# Power_Board.net
KiCad netlist of a schematic drawn in Altium Designer
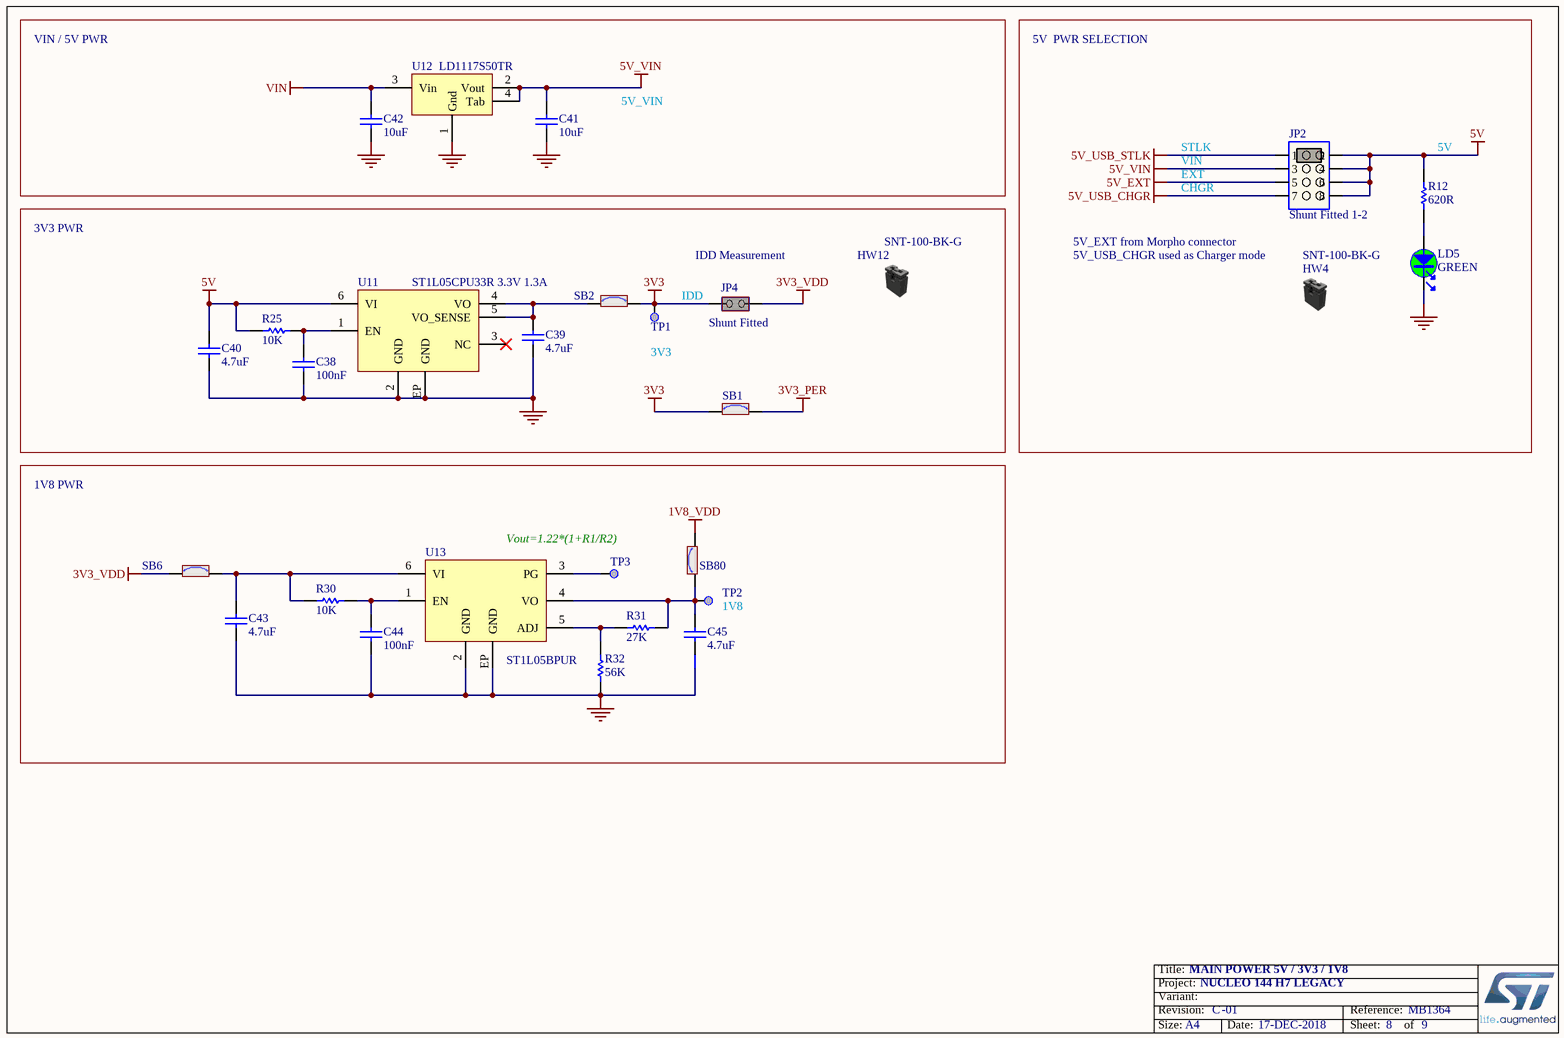
[diagram p0: Power_Board.SchDoc]

(export (version "E")
  (design (tool "Eeschema 10.0.6"))
  (components
    (comp (ref "C38")
      (value "100nF")
      (footprint "C0402")
      (description "Capacitor, MLCC, 100nF, 16V, X7R, 10%, 0402, T=0.5mm")
      (fields
        (field (name "INTERNAL_PART_NUMBER") "MCD-00006")
        (field (name "MANUFACTURER_PART_NUMBER") "CC0402KRX7R7BB104")
        (field (name "PROVIDED_BY") "SUBCO")
      )
      (libsource (lib "MCD_PARTS_database") (part "Capacitor"))
    )
    (comp (ref "C39")
      (value "4.7uF")
      (footprint "C0603")
      (description "Capacitor, MLCC, 4.7µF, 10V, X5R, 20%, 0603, T=0,8mm")
      (fields
        (field (name "INTERNAL_PART_NUMBER") "MCD-01121")
        (field (name "MANUFACTURER_PART_NUMBER") "GRM188R61A475ME15")
        (field (name "PROVIDED_BY") "SUBCO")
      )
      (libsource (lib "MCD_PARTS_database") (part "Capacitor"))
    )
    (comp (ref "C40")
      (value "4.7uF")
      (footprint "C0603")
      (description "Capacitor, MLCC, 4.7uF, 16V, X5R, 20%, 0603, T=0,8mm")
      (fields
        (field (name "INTERNAL_PART_NUMBER") "MCD-00097")
        (field (name "MANUFACTURER_PART_NUMBER") "GRM188R61C475KE11")
        (field (name "PROVIDED_BY") "SUBCO")
      )
      (libsource (lib "MCD_PARTS_database") (part "Capacitor"))
    )
    (comp (ref "C41")
      (value "10uF")
      (footprint "C0805")
      (description "Capacitor, MLCC, 10uF, 25V, X5R, 10%, 0805, T=0,85mm")
      (fields
        (field (name "INTERNAL_PART_NUMBER") "MCD-00014")
        (field (name "MANUFACTURER_PART_NUMBER") "CC0805KRX5R8BB106")
        (field (name "PROVIDED_BY") "SUBCO")
      )
      (libsource (lib "MCD_PARTS_database") (part "Capacitor"))
    )
    (comp (ref "C42")
      (value "10uF")
      (footprint "C0805")
      (description "Capacitor, MLCC, 10uF, 25V, X5R, 10%, 0805, T=0,85mm")
      (fields
        (field (name "INTERNAL_PART_NUMBER") "MCD-00014")
        (field (name "MANUFACTURER_PART_NUMBER") "CC0805KRX5R8BB106")
        (field (name "PROVIDED_BY") "SUBCO")
      )
      (libsource (lib "MCD_PARTS_database") (part "Capacitor"))
    )
    (comp (ref "C43")
      (value "4.7uF")
      (footprint "C0603")
      (description "Capacitor, MLCC, 4.7uF, 16V, X5R, 20%, 0603, T=0,8mm")
      (fields
        (field (name "INTERNAL_PART_NUMBER") "MCD-00097")
        (field (name "MANUFACTURER_PART_NUMBER") "GRM188R61C475KE11")
        (field (name "PROVIDED_BY") "SUBCO")
      )
      (libsource (lib "MCD_PARTS_database") (part "Capacitor"))
    )
    (comp (ref "C44")
      (value "100nF")
      (footprint "C0603")
      (description "Capacitor, MLCC, 100nF, 6V3, X5R, 10%, 0603, T=0,8mm")
      (fields
        (field (name "INTERNAL_PART_NUMBER") "MCD-00237")
        (field (name "MANUFACTURER_PART_NUMBER") "CC0603KRX5R5BB104")
        (field (name "PROVIDED_BY") "SUBCO")
      )
      (libsource (lib "MCD_PARTS_database") (part "Capacitor"))
    )
    (comp (ref "C45")
      (value "4.7uF")
      (footprint "C0603")
      (description "Capacitor, MLCC, 4.7µF, 10V, X5R, 20%, 0603, T=0,8mm")
      (fields
        (field (name "INTERNAL_PART_NUMBER") "MCD-01121")
        (field (name "MANUFACTURER_PART_NUMBER") "GRM188R61A475ME15")
        (field (name "PROVIDED_BY") "SUBCO")
      )
      (libsource (lib "MCD_PARTS_database") (part "Capacitor"))
    )
    (comp (ref "HW4")
      (value "SNT-100-BK-G")
      (description "SHUNT 2.54mm BLACK")
      (fields
        (field (name "INTERNAL_PART_NUMBER") "MCD-00043")
        (field (name "MANUFACTURER") "SAMTEC")
        (field (name "PROVIDED_BY") "SUBCO")
      )
      (libsource (lib "MCD_PARTS_database") (part "Shunt Black 2.54mm"))
    )
    (comp (ref "HW12")
      (value "SNT-100-BK-G")
      (description "SHUNT 2.54mm BLACK")
      (fields
        (field (name "INTERNAL_PART_NUMBER") "MCD-00043")
        (field (name "MANUFACTURER") "SAMTEC")
        (field (name "PROVIDED_BY") "SUBCO")
      )
      (libsource (lib "MCD_PARTS_database") (part "Shunt Black 2.54mm"))
    )
    (comp (ref "JP2")
      (value "Shunt Fitted 1-2")
      (footprint "CON_SAMTEC_TSW-104-07-X-D")
      (description "Header, 4x2, 2,54mm, VR, TH, Height 5.84mm/2.54mm - Shunt Fitted 1-2")
      (fields
        (field (name "INTERNAL_PART_NUMBER") "MCD-00686")
        (field (name "MANUFACTURER_PART_NUMBER") "TSW-104-07-x-D")
        (field (name "PROVIDED_BY") "SUBCO")
      )
      (libsource (lib "MCD_PARTS_database") (part "Jumper_Header 4x2 Fitted 1-2"))
    )
    (comp (ref "JP4")
      (value "Shunt Fitted")
      (footprint "CON_SAMTEC_TSW-102-07-G-S")
      (description "Header, 2x1, 2,54mm, VR, TH, Height 5.84mm/2.54mm - Shunt Fitted by default")
      (fields
        (field (name "INTERNAL_PART_NUMBER") "MCD-00683")
        (field (name "MANUFACTURER_PART_NUMBER") "TSW-102-07-x-S")
        (field (name "PROVIDED_BY") "SUBCO")
      )
      (libsource (lib "MCD_PARTS_database") (part "Jumper_Header 2x1 Fitted"))
    )
    (comp (ref "LD5")
      (value "GREEN")
      (footprint "LED_0603_OSRAM_LG-Q396-PS-35_GREEN_1A2K_H0P4")
      (description "LED Green, 0603 SMD, Forward Voltage Typ=2V, Max=2.5V")
      (fields
        (field (name "INTERNAL_PART_NUMBER") "MCD-00588")
        (field (name "MANUFACTURER_PART_NUMBER") "LG Q396-PS-35")
        (field (name "PROVIDED_BY") "SUBCO")
      )
      (libsource (lib "MCD_PARTS_database") (part "LED_green"))
    )
    (comp (ref "R12")
      (value "620R")
      (footprint "R0603")
      (description "Resistor,620R,0603,1%,1/10W")
      (fields
        (field (name "INTERNAL_PART_NUMBER") "MCD-00500")
        (field (name "MANUFACTURER_PART_NUMBER") "RC0603FR-07620RL")
        (field (name "PROVIDED_BY") "SUBCO")
      )
      (libsource (lib "MCD_PARTS_database") (part "Resistor"))
    )
    (comp (ref "R25")
      (value "10K")
      (footprint "R0402")
      (description "Resistor,10K,0402,1%,1/16W")
      (fields
        (field (name "INTERNAL_PART_NUMBER") "MCD-00053")
        (field (name "MANUFACTURER_PART_NUMBER") "RC0402FR-0710KL")
        (field (name "PROVIDED_BY") "SUBCO")
      )
      (libsource (lib "MCD_PARTS_database") (part "Resistor"))
    )
    (comp (ref "R30")
      (value "10K")
      (footprint "R0402")
      (description "Resistor,10K,0402,1%,1/16W")
      (fields
        (field (name "INTERNAL_PART_NUMBER") "MCD-00053")
        (field (name "MANUFACTURER_PART_NUMBER") "RC0402FR-0710KL")
        (field (name "PROVIDED_BY") "SUBCO")
      )
      (libsource (lib "MCD_PARTS_database") (part "Resistor"))
    )
    (comp (ref "R31")
      (value "27K")
      (footprint "R0402")
      (description "Resistor,27K,0402,1%,1/16W")
      (fields
        (field (name "INTERNAL_PART_NUMBER") "MCD-00443")
        (field (name "MANUFACTURER_PART_NUMBER") "RC0402FR-0727KL")
        (field (name "PROVIDED_BY") "SUBCO")
      )
      (libsource (lib "MCD_PARTS_database") (part "Resistor"))
    )
    (comp (ref "R32")
      (value "56K")
      (footprint "R0402")
      (description "Resistor,56K,0402,1%,1/16W")
      (fields
        (field (name "INTERNAL_PART_NUMBER") "MCD-00493")
        (field (name "MANUFACTURER_PART_NUMBER") "RC0402FR-0756KL")
        (field (name "PROVIDED_BY") "SUBCO")
      )
      (libsource (lib "MCD_PARTS_database") (part "Resistor"))
    )
    (comp (ref "SB1")
      (value "SB_ON")
      (footprint "SOLDER-BRIDGE_R0603-0R")
      (description "Solder Bridge ON")
      (fields
        (field (name "INTERNAL_PART_NUMBER") "MCD-00071")
        (field (name "MANUFACTURER_PART_NUMBER") "RC0603JR-070RL")
        (field (name "PROVIDED_BY") "SUBCO")
      )
      (libsource (lib "MCD_PARTS_database") (part "SB_ON"))
    )
    (comp (ref "SB2")
      (value "SB_ON")
      (footprint "SOLDER-BRIDGE_R0603-0R")
      (description "Solder Bridge ON")
      (fields
        (field (name "INTERNAL_PART_NUMBER") "MCD-00071")
        (field (name "MANUFACTURER_PART_NUMBER") "RC0603JR-070RL")
        (field (name "PROVIDED_BY") "SUBCO")
      )
      (libsource (lib "MCD_PARTS_database") (part "SB_ON"))
    )
    (comp (ref "SB6")
      (value "SB_ON")
      (footprint "SOLDER-BRIDGE_R0603-0R")
      (description "Solder Bridge ON")
      (fields
        (field (name "INTERNAL_PART_NUMBER") "MCD-00071")
        (field (name "MANUFACTURER_PART_NUMBER") "RC0603JR-070RL")
        (field (name "PROVIDED_BY") "SUBCO")
      )
      (libsource (lib "MCD_PARTS_database") (part "SB_ON"))
    )
    (comp (ref "SB80")
      (value "SB_ON")
      (footprint "SOLDER-BRIDGE_R0603-0R")
      (description "Solder Bridge ON")
      (fields
        (field (name "INTERNAL_PART_NUMBER") "MCD-00071")
        (field (name "MANUFACTURER_PART_NUMBER") "RC0603JR-070RL")
        (field (name "PROVIDED_BY") "SUBCO")
      )
      (libsource (lib "") (part "SB_ON_1"))
    )
    (comp (ref "TP1")
      (value "Test Point")
      (footprint "TP_SMD_1MM")
      (description "Test Point 1mm")
      (fields (field (name "INTERNAL_PART_NUMBER") "MCD-00074") (field (name "MANUFACTURER") "n/a"))
      (libsource (lib "") (part "Test Point_1"))
    )
    (comp (ref "TP2")
      (value "Test Point")
      (footprint "TP_SMD_1MM")
      (description "Test Point 1mm")
      (fields
        (field (name "INTERNAL_PART_NUMBER") "MCD-00074")
        (field (name "MANUFACTURER_PART_NUMBER") "n/a")
      )
      (libsource (lib "MCD_PARTS_database") (part "Test Point"))
    )
    (comp (ref "TP3")
      (value "Test Point")
      (footprint "TP_SMD_1MM")
      (description "Test Point 1mm")
      (fields
        (field (name "INTERNAL_PART_NUMBER") "MCD-00074")
        (field (name "MANUFACTURER_PART_NUMBER") "n/a")
      )
      (libsource (lib "MCD_PARTS_database") (part "Test Point"))
    )
    (comp (ref "U11")
      (value "ST1L05CPU33R 3.3V 1.3A")
      (footprint "ICC_DFN6-EPAD_3X3_P095")
      (description "LDO, 3.3V, 1.3A, Very low quiescent current BiCMOS voltage regulator")
      (fields
        (field (name "INTERNAL_PART_NUMBER") "MCD-01025")
        (field (name "MANUFACTURER_PART_NUMBER") "ST1L05CPU33R")
        (field (name "PROVIDED_BY") "SUBCO with ST control")
      )
      (libsource (lib "MCD_PARTS_database") (part "ST1L05CPU33R"))
    )
    (comp (ref "U12")
      (value "LD1117S50TR")
      (footprint "REG_SOT223-TAB")
      (description "IC REG LDO 5V 0.8A SOT223")
      (fields
        (field (name "INTERNAL_PART_NUMBER") "MCD-00088")
        (field (name "MANUFACTURER") "STMICROELECTRONICS")
        (field (name "PROVIDED_BY") "SUBCO with ST control")
      )
      (libsource (lib "MCD_PARTS_database") (part "LD1117S50TR"))
    )
    (comp (ref "U13")
      (value "ST1L05BPUR")
      (footprint "ICC_DFN6-EPAD_3X3_P095")
      (description "LDO Linear Voltage Regulator IC Positive Adjustable 1 Output Adjustable 1.3A 6-DFN (3x3)")
      (fields
        (field (name "INTERNAL_PART_NUMBER") "MCD-00581")
        (field (name "MANUFACTURER") "STMICROELECTRONICS")
        (field (name "PROVIDED_BY") "SUBCO with ST control")
      )
      (libsource (lib "MCD_PARTS_database") (part "ST1L05BPUR"))
    )
  )
  (nets
    (net (code "1") (name "1V8_VDD") (class "Default")
      (node (ref "SB80") (pin "2") (pinfunction "2_2") (pintype "passive"))
    )
    (net (code "2") (name "3V3") (class "Default")
      (node (ref "JP4") (pin "1") (pinfunction "COMMON_1") (pintype "passive"))
      (node (ref "SB1") (pin "1") (pinfunction "1_1") (pintype "passive"))
      (node (ref "SB2") (pin "2") (pinfunction "2_2") (pintype "passive"))
      (node (ref "TP1") (pin "1") (pinfunction "1_1") (pintype "passive"))
    )
    (net (code "3") (name "3V3_PER") (class "Default")
      (node (ref "SB1") (pin "2") (pinfunction "2_2") (pintype "passive"))
    )
    (net (code "4") (name "3V3_VDD") (class "Default")
      (node (ref "JP4") (pin "2") (pinfunction "NO_2") (pintype "passive"))
      (node (ref "SB6") (pin "1") (pinfunction "1_1") (pintype "passive"))
    )
    (net (code "5") (name "5V") (class "Default")
      (node (ref "C40") (pin "2") (pinfunction "2_2") (pintype "passive"))
      (node (ref "JP2") (pin "2") (pinfunction "2_2") (pintype "passive"))
      (node (ref "JP2") (pin "4") (pinfunction "4_4") (pintype "passive"))
      (node (ref "JP2") (pin "6") (pinfunction "6_6") (pintype "passive"))
      (node (ref "JP2") (pin "8") (pinfunction "8_8") (pintype "passive"))
      (node (ref "R12") (pin "2") (pinfunction "2_2") (pintype "passive"))
      (node (ref "R25") (pin "2") (pinfunction "2_2") (pintype "passive"))
      (node (ref "U11") (pin "6") (pinfunction "VI_6") (pintype "passive"))
    )
    (net (code "6") (name "5V_EXT") (class "Default")
      (node (ref "JP2") (pin "5") (pinfunction "5_5") (pintype "passive"))
    )
    (net (code "7") (name "5V_USB_CHGR") (class "Default")
      (node (ref "JP2") (pin "7") (pinfunction "7_7") (pintype "passive"))
    )
    (net (code "8") (name "5V_USB_STLK") (class "Default")
      (node (ref "JP2") (pin "1") (pinfunction "1_1") (pintype "passive"))
    )
    (net (code "9") (name "5V_VIN") (class "Default")
      (node (ref "C41") (pin "2") (pinfunction "2_2") (pintype "passive"))
      (node (ref "JP2") (pin "3") (pinfunction "3_3") (pintype "passive"))
      (node (ref "U12") (pin "2") (pinfunction "Vout_2") (pintype "passive"))
      (node (ref "U12") (pin "4") (pinfunction "Tab_4") (pintype "passive"))
    )
    (net (code "10") (name "GND") (class "Default")
      (node (ref "C38") (pin "2") (pinfunction "2_2") (pintype "passive"))
      (node (ref "C39") (pin "1") (pinfunction "1_1") (pintype "passive"))
      (node (ref "C40") (pin "1") (pinfunction "1_1") (pintype "passive"))
      (node (ref "C41") (pin "1") (pinfunction "1_1") (pintype "passive"))
      (node (ref "C42") (pin "1") (pinfunction "1_1") (pintype "passive"))
      (node (ref "C43") (pin "1") (pinfunction "1_1") (pintype "passive"))
      (node (ref "C44") (pin "1") (pinfunction "1_1") (pintype "passive"))
      (node (ref "C45") (pin "1") (pinfunction "1_1") (pintype "passive"))
      (node (ref "LD5") (pin "2") (pintype "passive"))
      (node (ref "R32") (pin "1") (pinfunction "1_1") (pintype "passive"))
      (node (ref "U11") (pin "2") (pinfunction "GND_2") (pintype "passive"))
      (node (ref "U11") (pin "EP") (pinfunction "GND_EP") (pintype "passive"))
      (node (ref "U12") (pin "1") (pinfunction "Gnd_1") (pintype "passive"))
      (node (ref "U13") (pin "2") (pinfunction "GND_2") (pintype "passive"))
      (node (ref "U13") (pin "EP") (pinfunction "GND_EP") (pintype "passive"))
    )
    (net (code "11") (name "Net-(LD5-Pad1)") (class "Default")
      (node (ref "LD5") (pin "1") (pintype "passive"))
      (node (ref "R12") (pin "1") (pinfunction "1_1") (pintype "passive"))
    )
    (net (code "12") (name "Net-(U11-EN)") (class "Default")
      (node (ref "C38") (pin "1") (pinfunction "1_1") (pintype "passive"))
      (node (ref "R25") (pin "1") (pinfunction "1_1") (pintype "passive"))
      (node (ref "U11") (pin "1") (pinfunction "EN_1") (pintype "passive"))
    )
    (net (code "13") (name "Net-(U11-VO)") (class "Default")
      (node (ref "C39") (pin "2") (pinfunction "2_2") (pintype "passive"))
      (node (ref "SB2") (pin "1") (pinfunction "1_1") (pintype "passive"))
      (node (ref "U11") (pin "4") (pinfunction "VO_4") (pintype "passive"))
      (node (ref "U11") (pin "5") (pinfunction "VO_SENSE_5") (pintype "passive"))
    )
    (net (code "14") (name "Net-(U13-ADJ)") (class "Default")
      (node (ref "R31") (pin "1") (pinfunction "1_1") (pintype "passive"))
      (node (ref "R32") (pin "2") (pinfunction "2_2") (pintype "passive"))
      (node (ref "U13") (pin "5") (pinfunction "ADJ_5") (pintype "passive"))
    )
    (net (code "15") (name "Net-(U13-EN)") (class "Default")
      (node (ref "C44") (pin "2") (pinfunction "2_2") (pintype "passive"))
      (node (ref "R30") (pin "1") (pinfunction "1_1") (pintype "passive"))
      (node (ref "U13") (pin "1") (pinfunction "EN_1") (pintype "passive"))
    )
    (net (code "16") (name "Net-(U13-PG)") (class "Default")
      (node (ref "TP3") (pin "1") (pinfunction "1_1") (pintype "passive"))
      (node (ref "U13") (pin "3") (pinfunction "PG_3") (pintype "passive"))
    )
    (net (code "17") (name "Net-(U13-VI)") (class "Default")
      (node (ref "C43") (pin "2") (pinfunction "2_2") (pintype "passive"))
      (node (ref "R30") (pin "2") (pinfunction "2_2") (pintype "passive"))
      (node (ref "SB6") (pin "2") (pinfunction "2_2") (pintype "passive"))
      (node (ref "U13") (pin "6") (pinfunction "VI_6") (pintype "passive"))
    )
    (net (code "18") (name "Net-(U13-VO)") (class "Default")
      (node (ref "C45") (pin "2") (pinfunction "2_2") (pintype "passive"))
      (node (ref "R31") (pin "2") (pinfunction "2_2") (pintype "passive"))
      (node (ref "SB80") (pin "1") (pinfunction "1_1") (pintype "passive"))
      (node (ref "TP2") (pin "1") (pinfunction "1_1") (pintype "passive"))
      (node (ref "U13") (pin "4") (pinfunction "VO_4") (pintype "passive"))
    )
    (net (code "19") (name "VIN") (class "Default")
      (node (ref "C42") (pin "2") (pinfunction "2_2") (pintype "passive"))
      (node (ref "U12") (pin "3") (pinfunction "Vin_3") (pintype "passive"))
    )
    (net (code "20") (name "unconnected-(U11-NC-Pad3)") (class "Default")
      (node (ref "U11") (pin "3") (pinfunction "NC_3") (pintype "passive+no_connect"))
    )
  )
)
